# Hex_Motor_Module.net
KiCad netlist of a schematic drawn in EAGLE
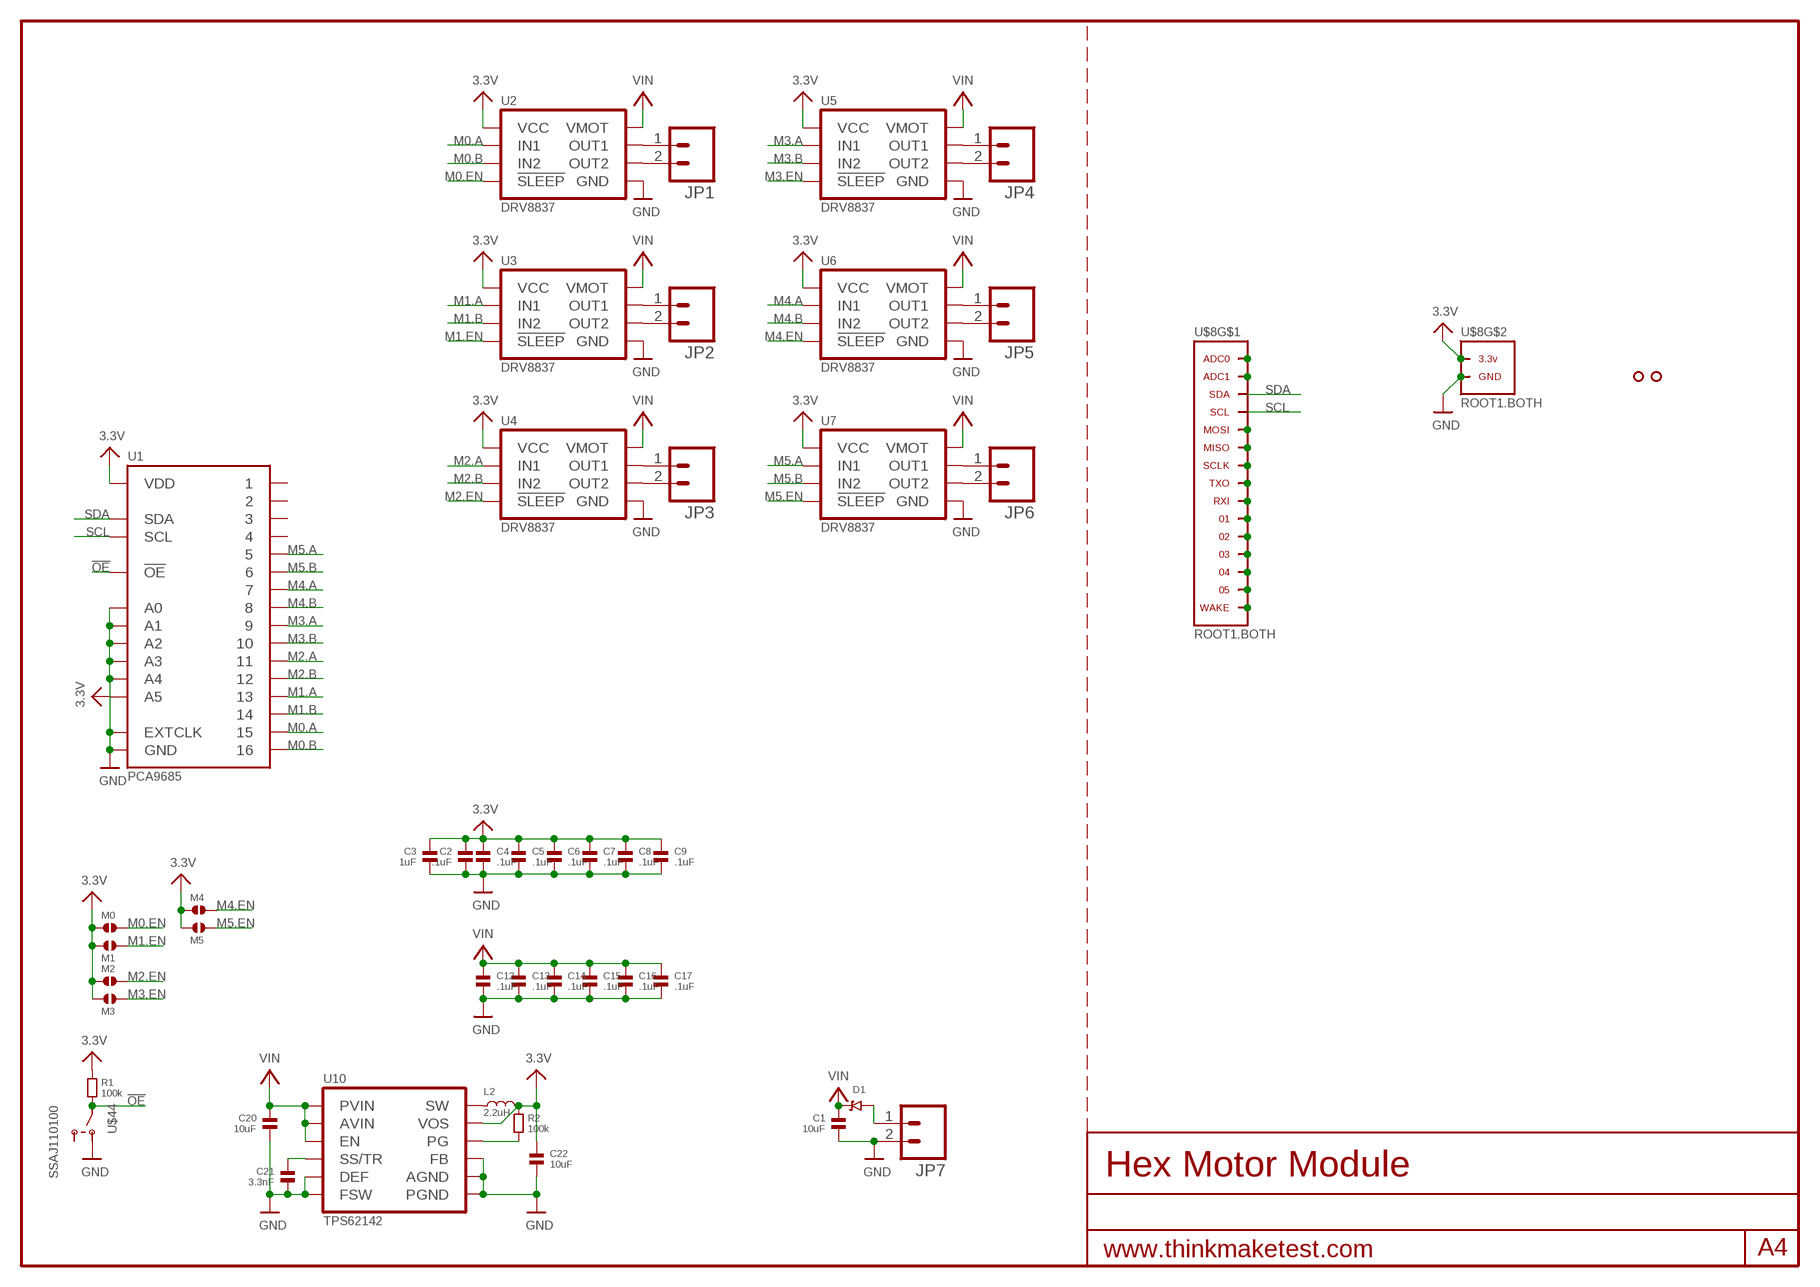
[diagram p0: schematic, sheet 1]

(export (version "E")
  (design (tool "Eeschema 10.0.6"))
  (components
    (comp (ref "C1")
      (value "10uF")
      (footprint "eagle-import:1206")
      (libsource (lib "eagle-import") (part "CAPACITOR.1206"))
    )
    (comp (ref "C2")
      (value ".1uF")
      (footprint "eagle-import:0603")
      (libsource (lib "eagle-import") (part "CAPACITOR.0603"))
    )
    (comp (ref "C3")
      (value "1uF")
      (footprint "eagle-import:0603")
      (libsource (lib "eagle-import") (part "CAPACITOR.0603"))
    )
    (comp (ref "C4")
      (value ".1uF")
      (footprint "eagle-import:0402")
      (libsource (lib "eagle-import") (part "CAPACITOR.0402"))
    )
    (comp (ref "C5")
      (value ".1uF")
      (footprint "eagle-import:0402")
      (libsource (lib "eagle-import") (part "CAPACITOR.0402"))
    )
    (comp (ref "C6")
      (value ".1uF")
      (footprint "eagle-import:0402")
      (libsource (lib "eagle-import") (part "CAPACITOR.0402"))
    )
    (comp (ref "C7")
      (value ".1uF")
      (footprint "eagle-import:0402")
      (libsource (lib "eagle-import") (part "CAPACITOR.0402"))
    )
    (comp (ref "C8")
      (value ".1uF")
      (footprint "eagle-import:0402")
      (libsource (lib "eagle-import") (part "CAPACITOR.0402"))
    )
    (comp (ref "C9")
      (value ".1uF")
      (footprint "eagle-import:0402")
      (libsource (lib "eagle-import") (part "CAPACITOR.0402"))
    )
    (comp (ref "C12")
      (value ".1uF")
      (footprint "eagle-import:0402")
      (libsource (lib "eagle-import") (part "CAPACITOR.0402"))
    )
    (comp (ref "C13")
      (value ".1uF")
      (footprint "eagle-import:0402")
      (libsource (lib "eagle-import") (part "CAPACITOR.0402"))
    )
    (comp (ref "C14")
      (value ".1uF")
      (footprint "eagle-import:0402")
      (libsource (lib "eagle-import") (part "CAPACITOR.0402"))
    )
    (comp (ref "C15")
      (value ".1uF")
      (footprint "eagle-import:0402")
      (libsource (lib "eagle-import") (part "CAPACITOR.0402"))
    )
    (comp (ref "C16")
      (value ".1uF")
      (footprint "eagle-import:0402")
      (libsource (lib "eagle-import") (part "CAPACITOR.0402"))
    )
    (comp (ref "C17")
      (value ".1uF")
      (footprint "eagle-import:0402")
      (libsource (lib "eagle-import") (part "CAPACITOR.0402"))
    )
    (comp (ref "C20")
      (value "10uF")
      (footprint "eagle-import:0805")
      (libsource (lib "eagle-import") (part "CAPACITOR.0805"))
    )
    (comp (ref "C21")
      (value "3.3nF")
      (footprint "eagle-import:0603")
      (libsource (lib "eagle-import") (part "CAPACITOR.0603"))
    )
    (comp (ref "C22")
      (value "10uF")
      (footprint "eagle-import:0805")
      (libsource (lib "eagle-import") (part "CAPACITOR.0805"))
    )
    (comp (ref "D1")
      (value "DIODE[SCHOTKY]-SOD123W")
      (footprint "eagle-import:SOD123W")
      (libsource (lib "eagle-import") (part "DIODE[SCHOTKY]-SOD123W"))
    )
    (comp (ref "JP1")
      (value "M023.5MM_LOCK")
      (footprint "eagle-import:SCREWTERMINAL-3.5MM-2_LOCK")
      (libsource (lib "eagle-import") (part "M023.5MM_LOCK"))
    )
    (comp (ref "JP2")
      (value "M023.5MM_LOCK")
      (footprint "eagle-import:SCREWTERMINAL-3.5MM-2_LOCK")
      (libsource (lib "eagle-import") (part "M023.5MM_LOCK"))
    )
    (comp (ref "JP3")
      (value "M023.5MM_LOCK")
      (footprint "eagle-import:SCREWTERMINAL-3.5MM-2_LOCK")
      (libsource (lib "eagle-import") (part "M023.5MM_LOCK"))
    )
    (comp (ref "JP4")
      (value "M023.5MM_LOCK")
      (footprint "eagle-import:SCREWTERMINAL-3.5MM-2_LOCK")
      (libsource (lib "eagle-import") (part "M023.5MM_LOCK"))
    )
    (comp (ref "JP5")
      (value "M023.5MM_LOCK")
      (footprint "eagle-import:SCREWTERMINAL-3.5MM-2_LOCK")
      (libsource (lib "eagle-import") (part "M023.5MM_LOCK"))
    )
    (comp (ref "JP6")
      (value "M023.5MM_LOCK")
      (footprint "eagle-import:SCREWTERMINAL-3.5MM-2_LOCK")
      (libsource (lib "eagle-import") (part "M023.5MM_LOCK"))
    )
    (comp (ref "JP7")
      (value "M023.5MM_LOCK")
      (footprint "eagle-import:SCREWTERMINAL-3.5MM-2_LOCK")
      (libsource (lib "eagle-import") (part "M023.5MM_LOCK"))
    )
    (comp (ref "L2")
      (value "2.2uH")
      (footprint "eagle-import:SRP4020")
      (libsource (lib "eagle-import") (part "INDUCTOR-SRP4020"))
    )
    (comp (ref "M0")
      (value "SOLDERJUMPER.2.LRG.PASTE")
      (footprint "eagle-import:2.LRG.PASTE")
      (libsource (lib "eagle-import") (part "SOLDERJUMPER.2.LRG.PASTE"))
    )
    (comp (ref "M1")
      (value "SOLDERJUMPER.2.LRG.PASTE")
      (footprint "eagle-import:2.LRG.PASTE")
      (libsource (lib "eagle-import") (part "SOLDERJUMPER.2.LRG.PASTE"))
    )
    (comp (ref "M2")
      (value "SOLDERJUMPER.2.LRG.PASTE")
      (footprint "eagle-import:2.LRG.PASTE")
      (libsource (lib "eagle-import") (part "SOLDERJUMPER.2.LRG.PASTE"))
    )
    (comp (ref "M3")
      (value "SOLDERJUMPER.2.LRG.PASTE")
      (footprint "eagle-import:2.LRG.PASTE")
      (libsource (lib "eagle-import") (part "SOLDERJUMPER.2.LRG.PASTE"))
    )
    (comp (ref "M4")
      (value "SOLDERJUMPER.2.LRG.PASTE")
      (footprint "eagle-import:2.LRG.PASTE")
      (libsource (lib "eagle-import") (part "SOLDERJUMPER.2.LRG.PASTE"))
    )
    (comp (ref "M5")
      (value "SOLDERJUMPER.2.LRG.PASTE")
      (footprint "eagle-import:2.LRG.PASTE")
      (libsource (lib "eagle-import") (part "SOLDERJUMPER.2.LRG.PASTE"))
    )
    (comp (ref "R1")
      (value "100k")
      (footprint "eagle-import:0603")
      (libsource (lib "eagle-import") (part "RESISTOR.0603"))
    )
    (comp (ref "R2")
      (value "100k")
      (footprint "eagle-import:0603")
      (libsource (lib "eagle-import") (part "RESISTOR.0603"))
    )
    (comp (ref "U$3")
      (value "HOLE.2MM")
      (footprint "eagle-import:2MM")
      (libsource (lib "eagle-import") (part "HOLE.2MM"))
    )
    (comp (ref "U$4")
      (value "HOLE.2MM")
      (footprint "eagle-import:2MM")
      (libsource (lib "eagle-import") (part "HOLE.2MM"))
    )
    (comp (ref "U$8")
      (value "ROOT1.BOTH")
      (footprint "eagle-import:ROOT1.BOTH")
      (libsource (lib "eagle-import") (part "ROOT1.BOTH"))
    )
    (comp (ref "U$44")
      (value "SSAJ110100")
      (footprint "eagle-import:SSAJ110100")
      (libsource (lib "eagle-import") (part "SSAJ110100"))
    )
    (comp (ref "U1")
      (value "PCA9685")
      (footprint "eagle-import:HVQFN28")
      (libsource (lib "eagle-import") (part "PCA9685"))
    )
    (comp (ref "U2")
      (value "DRV8837")
      (footprint "eagle-import:DSG")
      (libsource (lib "eagle-import") (part "DRV8837"))
    )
    (comp (ref "U3")
      (value "DRV8837")
      (footprint "eagle-import:DSG")
      (libsource (lib "eagle-import") (part "DRV8837"))
    )
    (comp (ref "U4")
      (value "DRV8837")
      (footprint "eagle-import:DSG")
      (libsource (lib "eagle-import") (part "DRV8837"))
    )
    (comp (ref "U5")
      (value "DRV8837")
      (footprint "eagle-import:DSG")
      (libsource (lib "eagle-import") (part "DRV8837"))
    )
    (comp (ref "U6")
      (value "DRV8837")
      (footprint "eagle-import:DSG")
      (libsource (lib "eagle-import") (part "DRV8837"))
    )
    (comp (ref "U7")
      (value "DRV8837")
      (footprint "eagle-import:DSG")
      (libsource (lib "eagle-import") (part "DRV8837"))
    )
    (comp (ref "U10")
      (value "TPS62142")
      (footprint "eagle-import:RGT")
      (libsource (lib "eagle-import") (part "TPS6214X"))
    )
  )
  (nets
    (net (code "1") (name "/M0.A") (class "Default")
      (node (ref "U1") (pin "21") (pinfunction "15_21") (pintype "bidirectional"))
      (node (ref "U2") (pin "6") (pinfunction "IN1_6") (pintype "bidirectional"))
    )
    (net (code "2") (name "/M0.B") (class "Default")
      (node (ref "U1") (pin "22") (pinfunction "16_22") (pintype "bidirectional"))
      (node (ref "U2") (pin "5") (pinfunction "IN2_5") (pintype "bidirectional"))
    )
    (net (code "3") (name "/M0.EN") (class "Default")
      (node (ref "M0") (pin "2") (pinfunction "2_2") (pintype "bidirectional"))
      (node (ref "U2") (pin "7") (pinfunction "~{SLEEP}_7") (pintype "bidirectional"))
    )
    (net (code "4") (name "/M1.A") (class "Default")
      (node (ref "U1") (pin "19") (pinfunction "13_19") (pintype "bidirectional"))
      (node (ref "U3") (pin "6") (pinfunction "IN1_6") (pintype "bidirectional"))
    )
    (net (code "5") (name "/M1.B") (class "Default")
      (node (ref "U1") (pin "20") (pinfunction "14_20") (pintype "bidirectional"))
      (node (ref "U3") (pin "5") (pinfunction "IN2_5") (pintype "bidirectional"))
    )
    (net (code "6") (name "/M1.EN") (class "Default")
      (node (ref "M1") (pin "2") (pinfunction "2_2") (pintype "bidirectional"))
      (node (ref "U3") (pin "7") (pinfunction "~{SLEEP}_7") (pintype "bidirectional"))
    )
    (net (code "7") (name "/M2.A") (class "Default")
      (node (ref "U1") (pin "17") (pinfunction "11_17") (pintype "bidirectional"))
      (node (ref "U4") (pin "6") (pinfunction "IN1_6") (pintype "bidirectional"))
    )
    (net (code "8") (name "/M2.B") (class "Default")
      (node (ref "U1") (pin "18") (pinfunction "12_18") (pintype "bidirectional"))
      (node (ref "U4") (pin "5") (pinfunction "IN2_5") (pintype "bidirectional"))
    )
    (net (code "9") (name "/M2.EN") (class "Default")
      (node (ref "M2") (pin "2") (pinfunction "2_2") (pintype "bidirectional"))
      (node (ref "U4") (pin "7") (pinfunction "~{SLEEP}_7") (pintype "bidirectional"))
    )
    (net (code "10") (name "/M3.A") (class "Default")
      (node (ref "U1") (pin "15") (pinfunction "9_15") (pintype "bidirectional"))
      (node (ref "U5") (pin "6") (pinfunction "IN1_6") (pintype "bidirectional"))
    )
    (net (code "11") (name "/M3.B") (class "Default")
      (node (ref "U1") (pin "16") (pinfunction "10_16") (pintype "bidirectional"))
      (node (ref "U5") (pin "5") (pinfunction "IN2_5") (pintype "bidirectional"))
    )
    (net (code "12") (name "/M3.EN") (class "Default")
      (node (ref "M3") (pin "2") (pinfunction "2_2") (pintype "bidirectional"))
      (node (ref "U5") (pin "7") (pinfunction "~{SLEEP}_7") (pintype "bidirectional"))
    )
    (net (code "13") (name "/M4.A") (class "Default")
      (node (ref "U1") (pin "12") (pinfunction "7_12") (pintype "bidirectional"))
      (node (ref "U6") (pin "6") (pinfunction "IN1_6") (pintype "bidirectional"))
    )
    (net (code "14") (name "/M4.B") (class "Default")
      (node (ref "U1") (pin "13") (pinfunction "8_13") (pintype "bidirectional"))
      (node (ref "U6") (pin "5") (pinfunction "IN2_5") (pintype "bidirectional"))
    )
    (net (code "15") (name "/M4.EN") (class "Default")
      (node (ref "M4") (pin "2") (pinfunction "2_2") (pintype "bidirectional"))
      (node (ref "U6") (pin "7") (pinfunction "~{SLEEP}_7") (pintype "bidirectional"))
    )
    (net (code "16") (name "/M5.A") (class "Default")
      (node (ref "U1") (pin "10") (pinfunction "5_10") (pintype "bidirectional"))
      (node (ref "U7") (pin "6") (pinfunction "IN1_6") (pintype "bidirectional"))
    )
    (net (code "17") (name "/M5.B") (class "Default")
      (node (ref "U1") (pin "11") (pinfunction "6_11") (pintype "bidirectional"))
      (node (ref "U7") (pin "5") (pinfunction "IN2_5") (pintype "bidirectional"))
    )
    (net (code "18") (name "/M5.EN") (class "Default")
      (node (ref "M5") (pin "2") (pinfunction "2_2") (pintype "bidirectional"))
      (node (ref "U7") (pin "7") (pinfunction "~{SLEEP}_7") (pintype "bidirectional"))
    )
    (net (code "19") (name "/SCL") (class "Default")
      (node (ref "U$8") (pin "SCL") (pinfunction "SCL_SCL") (pintype "bidirectional"))
      (node (ref "U$8") (pin "SCL@1") (pinfunction "SCL_SCL@1") (pintype "bidirectional"))
      (node (ref "U$8") (pin "SCL@VIA") (pinfunction "SCL_SCL@VIA") (pintype "bidirectional"))
      (node (ref "U1") (pin "26") (pinfunction "SCL_26") (pintype "bidirectional"))
    )
    (net (code "20") (name "/SDA") (class "Default")
      (node (ref "U$8") (pin "SDA") (pinfunction "SDA_SDA") (pintype "bidirectional"))
      (node (ref "U$8") (pin "SDA@1") (pinfunction "SDA_SDA@1") (pintype "bidirectional"))
      (node (ref "U$8") (pin "SDA@VIA") (pinfunction "SDA_SDA@VIA") (pintype "bidirectional"))
      (node (ref "U1") (pin "27") (pinfunction "SDA_27") (pintype "bidirectional"))
    )
    (net (code "21") (name "/~{OE}") (class "Default")
      (node (ref "R1") (pin "2") (pinfunction "2_2") (pintype "bidirectional"))
      (node (ref "U$44") (pin "C") (pinfunction "1_C") (pintype "bidirectional"))
      (node (ref "U1") (pin "23") (pinfunction "~{OE}_23") (pintype "bidirectional"))
    )
    (net (code "22") (name "3.3V") (class "Default")
      (node (ref "C2") (pin "1") (pinfunction "1_1") (pintype "bidirectional"))
      (node (ref "C22") (pin "1") (pinfunction "1_1") (pintype "bidirectional"))
      (node (ref "C3") (pin "1") (pinfunction "1_1") (pintype "bidirectional"))
      (node (ref "C4") (pin "1") (pinfunction "1_1") (pintype "bidirectional"))
      (node (ref "C5") (pin "1") (pinfunction "1_1") (pintype "bidirectional"))
      (node (ref "C6") (pin "1") (pinfunction "1_1") (pintype "bidirectional"))
      (node (ref "C7") (pin "1") (pinfunction "1_1") (pintype "bidirectional"))
      (node (ref "C8") (pin "1") (pinfunction "1_1") (pintype "bidirectional"))
      (node (ref "C9") (pin "1") (pinfunction "1_1") (pintype "bidirectional"))
      (node (ref "L2") (pin "2") (pinfunction "2_2") (pintype "passive"))
      (node (ref "M0") (pin "1") (pinfunction "1_1") (pintype "bidirectional"))
      (node (ref "M1") (pin "1") (pinfunction "1_1") (pintype "bidirectional"))
      (node (ref "M2") (pin "1") (pinfunction "1_1") (pintype "bidirectional"))
      (node (ref "M3") (pin "1") (pinfunction "1_1") (pintype "bidirectional"))
      (node (ref "M4") (pin "1") (pinfunction "1_1") (pintype "bidirectional"))
      (node (ref "M5") (pin "1") (pinfunction "1_1") (pintype "bidirectional"))
      (node (ref "R1") (pin "1") (pinfunction "1_1") (pintype "bidirectional"))
      (node (ref "R2") (pin "1") (pinfunction "1_1") (pintype "bidirectional"))
      (node (ref "U$8") (pin "3.3V@1") (pinfunction "3.3V_3.3V@1") (pintype "bidirectional"))
      (node (ref "U$8") (pin "3.3V@10") (pinfunction "3.3V_3.3V@10") (pintype "bidirectional"))
      (node (ref "U$8") (pin "3.3V@2") (pinfunction "3.3V_3.3V@2") (pintype "bidirectional"))
      (node (ref "U$8") (pin "3.3V@3") (pinfunction "3.3V_3.3V@3") (pintype "bidirectional"))
      (node (ref "U$8") (pin "3.3V@4") (pinfunction "3.3V_3.3V@4") (pintype "bidirectional"))
      (node (ref "U$8") (pin "3.3V@5") (pinfunction "3.3V_3.3V@5") (pintype "bidirectional"))
      (node (ref "U$8") (pin "3.3V@6") (pinfunction "3.3V_3.3V@6") (pintype "bidirectional"))
      (node (ref "U$8") (pin "3.3V@7") (pinfunction "3.3V_3.3V@7") (pintype "bidirectional"))
      (node (ref "U$8") (pin "3.3V@8") (pinfunction "3.3V_3.3V@8") (pintype "bidirectional"))
      (node (ref "U$8") (pin "3.3V@9") (pinfunction "3.3V_3.3V@9") (pintype "bidirectional"))
      (node (ref "U$8") (pin "3.3V@VIA") (pinfunction "3.3V_3.3V@VIA") (pintype "bidirectional"))
      (node (ref "U1") (pin "24") (pinfunction "A5_24") (pintype "bidirectional"))
      (node (ref "U1") (pin "28") (pinfunction "VDD_28") (pintype "bidirectional"))
      (node (ref "U10") (pin "14") (pinfunction "VOS_14") (pintype "bidirectional"))
      (node (ref "U2") (pin "8") (pinfunction "VCC_8") (pintype "bidirectional"))
      (node (ref "U3") (pin "8") (pinfunction "VCC_8") (pintype "bidirectional"))
      (node (ref "U4") (pin "8") (pinfunction "VCC_8") (pintype "bidirectional"))
      (node (ref "U5") (pin "8") (pinfunction "VCC_8") (pintype "bidirectional"))
      (node (ref "U6") (pin "8") (pinfunction "VCC_8") (pintype "bidirectional"))
      (node (ref "U7") (pin "8") (pinfunction "VCC_8") (pintype "bidirectional"))
    )
    (net (code "23") (name "GND") (class "Default")
      (node (ref "C1") (pin "2") (pinfunction "2_2") (pintype "bidirectional"))
      (node (ref "C12") (pin "2") (pinfunction "2_2") (pintype "bidirectional"))
      (node (ref "C13") (pin "2") (pinfunction "2_2") (pintype "bidirectional"))
      (node (ref "C14") (pin "2") (pinfunction "2_2") (pintype "bidirectional"))
      (node (ref "C15") (pin "2") (pinfunction "2_2") (pintype "bidirectional"))
      (node (ref "C16") (pin "2") (pinfunction "2_2") (pintype "bidirectional"))
      (node (ref "C17") (pin "2") (pinfunction "2_2") (pintype "bidirectional"))
      (node (ref "C2") (pin "2") (pinfunction "2_2") (pintype "bidirectional"))
      (node (ref "C20") (pin "2") (pinfunction "2_2") (pintype "bidirectional"))
      (node (ref "C21") (pin "2") (pinfunction "2_2") (pintype "bidirectional"))
      (node (ref "C22") (pin "2") (pinfunction "2_2") (pintype "bidirectional"))
      (node (ref "C3") (pin "2") (pinfunction "2_2") (pintype "bidirectional"))
      (node (ref "C4") (pin "2") (pinfunction "2_2") (pintype "bidirectional"))
      (node (ref "C5") (pin "2") (pinfunction "2_2") (pintype "bidirectional"))
      (node (ref "C6") (pin "2") (pinfunction "2_2") (pintype "bidirectional"))
      (node (ref "C7") (pin "2") (pinfunction "2_2") (pintype "bidirectional"))
      (node (ref "C8") (pin "2") (pinfunction "2_2") (pintype "bidirectional"))
      (node (ref "C9") (pin "2") (pinfunction "2_2") (pintype "bidirectional"))
      (node (ref "JP7") (pin "2") (pinfunction "2_2") (pintype "passive"))
      (node (ref "U$44") (pin "1") (pinfunction "2_1") (pintype "bidirectional"))
      (node (ref "U$8") (pin "GND@1") (pinfunction "GND_GND@1") (pintype "bidirectional"))
      (node (ref "U$8") (pin "GND@10") (pinfunction "GND_GND@10") (pintype "bidirectional"))
      (node (ref "U$8") (pin "GND@11") (pinfunction "GND_GND@11") (pintype "bidirectional"))
      (node (ref "U$8") (pin "GND@12") (pinfunction "GND_GND@12") (pintype "bidirectional"))
      (node (ref "U$8") (pin "GND@13") (pinfunction "GND_GND@13") (pintype "bidirectional"))
      (node (ref "U$8") (pin "GND@14") (pinfunction "GND_GND@14") (pintype "bidirectional"))
      (node (ref "U$8") (pin "GND@15") (pinfunction "GND_GND@15") (pintype "bidirectional"))
      (node (ref "U$8") (pin "GND@16") (pinfunction "GND_GND@16") (pintype "bidirectional"))
      (node (ref "U$8") (pin "GND@17") (pinfunction "GND_GND@17") (pintype "bidirectional"))
      (node (ref "U$8") (pin "GND@18") (pinfunction "GND_GND@18") (pintype "bidirectional"))
      (node (ref "U$8") (pin "GND@19") (pinfunction "GND_GND@19") (pintype "bidirectional"))
      (node (ref "U$8") (pin "GND@2") (pinfunction "GND_GND@2") (pintype "bidirectional"))
      (node (ref "U$8") (pin "GND@20") (pinfunction "GND_GND@20") (pintype "bidirectional"))
      (node (ref "U$8") (pin "GND@3") (pinfunction "GND_GND@3") (pintype "bidirectional"))
      (node (ref "U$8") (pin "GND@4") (pinfunction "GND_GND@4") (pintype "bidirectional"))
      (node (ref "U$8") (pin "GND@5") (pinfunction "GND_GND@5") (pintype "bidirectional"))
      (node (ref "U$8") (pin "GND@6") (pinfunction "GND_GND@6") (pintype "bidirectional"))
      (node (ref "U$8") (pin "GND@7") (pinfunction "GND_GND@7") (pintype "bidirectional"))
      (node (ref "U$8") (pin "GND@8") (pinfunction "GND_GND@8") (pintype "bidirectional"))
      (node (ref "U$8") (pin "GND@9") (pinfunction "GND_GND@9") (pintype "bidirectional"))
      (node (ref "U$8") (pin "GND@VIA") (pinfunction "GND_GND@VIA") (pintype "bidirectional"))
      (node (ref "U1") (pin "1") (pinfunction "A0_1") (pintype "bidirectional"))
      (node (ref "U1") (pin "14") (pinfunction "GND_14") (pintype "bidirectional"))
      (node (ref "U1") (pin "2") (pinfunction "A1_2") (pintype "bidirectional"))
      (node (ref "U1") (pin "25") (pinfunction "EXTCLK_25") (pintype "bidirectional"))
      (node (ref "U1") (pin "3") (pinfunction "A2_3") (pintype "bidirectional"))
      (node (ref "U1") (pin "4") (pinfunction "A3_4") (pintype "bidirectional"))
      (node (ref "U1") (pin "5") (pinfunction "A4_5") (pintype "bidirectional"))
      (node (ref "U1") (pin "PAD") (pinfunction "GND_PAD") (pintype "bidirectional"))
      (node (ref "U10") (pin "15") (pinfunction "PGND_15") (pintype "bidirectional"))
      (node (ref "U10") (pin "16") (pinfunction "PGND_16") (pintype "bidirectional"))
      (node (ref "U10") (pin "5") (pinfunction "FB_5") (pintype "bidirectional"))
      (node (ref "U10") (pin "6") (pinfunction "AGND_6") (pintype "bidirectional"))
      (node (ref "U10") (pin "7") (pinfunction "FSW_7") (pintype "bidirectional"))
      (node (ref "U10") (pin "8") (pinfunction "DEF_8") (pintype "bidirectional"))
      (node (ref "U10") (pin "PAD") (pinfunction "AGND_PAD") (pintype "bidirectional"))
      (node (ref "U2") (pin "4") (pinfunction "GND_4") (pintype "bidirectional"))
      (node (ref "U2") (pin "PAD") (pinfunction "GND_PAD") (pintype "bidirectional"))
      (node (ref "U3") (pin "4") (pinfunction "GND_4") (pintype "bidirectional"))
      (node (ref "U3") (pin "PAD") (pinfunction "GND_PAD") (pintype "bidirectional"))
      (node (ref "U4") (pin "4") (pinfunction "GND_4") (pintype "bidirectional"))
      (node (ref "U4") (pin "PAD") (pinfunction "GND_PAD") (pintype "bidirectional"))
      (node (ref "U5") (pin "4") (pinfunction "GND_4") (pintype "bidirectional"))
      (node (ref "U5") (pin "PAD") (pinfunction "GND_PAD") (pintype "bidirectional"))
      (node (ref "U6") (pin "4") (pinfunction "GND_4") (pintype "bidirectional"))
      (node (ref "U6") (pin "PAD") (pinfunction "GND_PAD") (pintype "bidirectional"))
      (node (ref "U7") (pin "4") (pinfunction "GND_4") (pintype "bidirectional"))
      (node (ref "U7") (pin "PAD") (pinfunction "GND_PAD") (pintype "bidirectional"))
    )
    (net (code "24") (name "Net-(D1-1)") (class "Default")
      (node (ref "D1") (pin "P$1") (pinfunction "1_P$1") (pintype "bidirectional"))
      (node (ref "JP7") (pin "1") (pinfunction "1_1") (pintype "passive"))
    )
    (net (code "25") (name "Net-(L2-Pad1)") (class "Default")
      (node (ref "L2") (pin "1") (pinfunction "1_1") (pintype "passive"))
      (node (ref "U10") (pin "1") (pinfunction "SW_1") (pintype "bidirectional"))
      (node (ref "U10") (pin "2") (pinfunction "SW_2") (pintype "bidirectional"))
      (node (ref "U10") (pin "3") (pinfunction "SW_3") (pintype "bidirectional"))
    )
    (net (code "26") (name "Net-(U$8-PadADC0)") (class "Default")
      (node (ref "U$8") (pin "ADC0") (pinfunction "ADC0_ADC0") (pintype "bidirectional"))
      (node (ref "U$8") (pin "ADC0@1") (pinfunction "ADC0_ADC0@1") (pintype "bidirectional"))
      (node (ref "U$8") (pin "ADC0@VIA") (pinfunction "ADC0_ADC0@VIA") (pintype "bidirectional"))
    )
    (net (code "27") (name "Net-(U$8-PadADC1)") (class "Default")
      (node (ref "U$8") (pin "ADC1") (pinfunction "ADC1_ADC1") (pintype "bidirectional"))
      (node (ref "U$8") (pin "ADC1@1") (pinfunction "ADC1_ADC1@1") (pintype "bidirectional"))
      (node (ref "U$8") (pin "ADC1@VIA") (pinfunction "ADC1_ADC1@VIA") (pintype "bidirectional"))
    )
    (net (code "28") (name "Net-(U$8-PadMISO)") (class "Default")
      (node (ref "U$8") (pin "MISO") (pinfunction "MISO_MISO") (pintype "bidirectional"))
      (node (ref "U$8") (pin "MISO@1") (pinfunction "MISO_MISO@1") (pintype "bidirectional"))
      (node (ref "U$8") (pin "MISO@VIA") (pinfunction "MISO_MISO@VIA") (pintype "bidirectional"))
    )
    (net (code "29") (name "Net-(U$8-PadMOSI)") (class "Default")
      (node (ref "U$8") (pin "MOSI") (pinfunction "MOSI_MOSI") (pintype "bidirectional"))
      (node (ref "U$8") (pin "MOSI@1") (pinfunction "MOSI_MOSI@1") (pintype "bidirectional"))
      (node (ref "U$8") (pin "MOSI@VIA") (pinfunction "MOSI_MOSI@VIA") (pintype "bidirectional"))
    )
    (net (code "30") (name "Net-(U$8-PadSCLK)") (class "Default")
      (node (ref "U$8") (pin "SCLK") (pinfunction "SCLK_SCLK") (pintype "bidirectional"))
      (node (ref "U$8") (pin "SCLK@1") (pinfunction "SCLK_SCLK@1") (pintype "bidirectional"))
      (node (ref "U$8") (pin "SCLK@VIA") (pinfunction "SCLK_SCLK@VIA") (pintype "bidirectional"))
    )
    (net (code "31") (name "Net-(U$8-PadWAKE)") (class "Default")
      (node (ref "U$8") (pin "WAKE") (pinfunction "WAKE_WAKE") (pintype "bidirectional"))
      (node (ref "U$8") (pin "WAKE@1") (pinfunction "WAKE_WAKE@1") (pintype "bidirectional"))
      (node (ref "U$8") (pin "WAKE@VIA") (pinfunction "WAKE_WAKE@VIA") (pintype "bidirectional"))
    )
    (net (code "32") (name "Net-(U$8A-01-Pad03)") (class "Default")
      (node (ref "U$8") (pin "03") (pinfunction "01_03") (pintype "bidirectional"))
      (node (ref "U$8") (pin "03@1") (pinfunction "01_03@1") (pintype "bidirectional"))
      (node (ref "U$8") (pin "03@VIA") (pinfunction "01_03@VIA") (pintype "bidirectional"))
    )
    (net (code "33") (name "Net-(U$8A-02-Pad04)") (class "Default")
      (node (ref "U$8") (pin "04") (pinfunction "02_04") (pintype "bidirectional"))
      (node (ref "U$8") (pin "04@1") (pinfunction "02_04@1") (pintype "bidirectional"))
      (node (ref "U$8") (pin "04@VIA") (pinfunction "02_04@VIA") (pintype "bidirectional"))
    )
    (net (code "34") (name "Net-(U$8A-03-Pad05)") (class "Default")
      (node (ref "U$8") (pin "05") (pinfunction "03_05") (pintype "bidirectional"))
      (node (ref "U$8") (pin "05@1") (pinfunction "03_05@1") (pintype "bidirectional"))
      (node (ref "U$8") (pin "05@VIA") (pinfunction "03_05@VIA") (pintype "bidirectional"))
    )
    (net (code "35") (name "Net-(U$8A-04-Pad06)") (class "Default")
      (node (ref "U$8") (pin "06") (pinfunction "04_06") (pintype "bidirectional"))
      (node (ref "U$8") (pin "06@1") (pinfunction "04_06@1") (pintype "bidirectional"))
      (node (ref "U$8") (pin "06@VIA") (pinfunction "04_06@VIA") (pintype "bidirectional"))
    )
    (net (code "36") (name "Net-(U$8A-05-Pad07)") (class "Default")
      (node (ref "U$8") (pin "07") (pinfunction "05_07") (pintype "bidirectional"))
      (node (ref "U$8") (pin "07@1") (pinfunction "05_07@1") (pintype "bidirectional"))
      (node (ref "U$8") (pin "07@VIA") (pinfunction "05_07@VIA") (pintype "bidirectional"))
    )
    (net (code "37") (name "Net-(U$8A-RXI-Pad02)") (class "Default")
      (node (ref "U$8") (pin "02") (pinfunction "RXI_02") (pintype "bidirectional"))
      (node (ref "U$8") (pin "02@1") (pinfunction "RXI_02@1") (pintype "bidirectional"))
      (node (ref "U$8") (pin "02@VIA") (pinfunction "RXI_02@VIA") (pintype "bidirectional"))
    )
    (net (code "38") (name "Net-(U$8A-TXO-Pad01)") (class "Default")
      (node (ref "U$8") (pin "01") (pinfunction "TXO_01") (pintype "bidirectional"))
      (node (ref "U$8") (pin "01@1") (pinfunction "TXO_01@1") (pintype "bidirectional"))
      (node (ref "U$8") (pin "01@VIA") (pinfunction "TXO_01@VIA") (pintype "bidirectional"))
    )
    (net (code "39") (name "Net-(U2-OUT1)") (class "Default")
      (node (ref "JP1") (pin "1") (pinfunction "1_1") (pintype "passive"))
      (node (ref "U2") (pin "2") (pinfunction "OUT1_2") (pintype "bidirectional"))
    )
    (net (code "40") (name "Net-(U2-OUT2)") (class "Default")
      (node (ref "JP1") (pin "2") (pinfunction "2_2") (pintype "passive"))
      (node (ref "U2") (pin "3") (pinfunction "OUT2_3") (pintype "bidirectional"))
    )
    (net (code "41") (name "Net-(U3-OUT1)") (class "Default")
      (node (ref "JP2") (pin "1") (pinfunction "1_1") (pintype "passive"))
      (node (ref "U3") (pin "2") (pinfunction "OUT1_2") (pintype "bidirectional"))
    )
    (net (code "42") (name "Net-(U3-OUT2)") (class "Default")
      (node (ref "JP2") (pin "2") (pinfunction "2_2") (pintype "passive"))
      (node (ref "U3") (pin "3") (pinfunction "OUT2_3") (pintype "bidirectional"))
    )
    (net (code "43") (name "Net-(U4-OUT1)") (class "Default")
      (node (ref "JP3") (pin "1") (pinfunction "1_1") (pintype "passive"))
      (node (ref "U4") (pin "2") (pinfunction "OUT1_2") (pintype "bidirectional"))
    )
    (net (code "44") (name "Net-(U4-OUT2)") (class "Default")
      (node (ref "JP3") (pin "2") (pinfunction "2_2") (pintype "passive"))
      (node (ref "U4") (pin "3") (pinfunction "OUT2_3") (pintype "bidirectional"))
    )
    (net (code "45") (name "Net-(U5-OUT1)") (class "Default")
      (node (ref "JP4") (pin "1") (pinfunction "1_1") (pintype "passive"))
      (node (ref "U5") (pin "2") (pinfunction "OUT1_2") (pintype "bidirectional"))
    )
    (net (code "46") (name "Net-(U5-OUT2)") (class "Default")
      (node (ref "JP4") (pin "2") (pinfunction "2_2") (pintype "passive"))
      (node (ref "U5") (pin "3") (pinfunction "OUT2_3") (pintype "bidirectional"))
    )
    (net (code "47") (name "Net-(U6-OUT1)") (class "Default")
      (node (ref "JP5") (pin "1") (pinfunction "1_1") (pintype "passive"))
      (node (ref "U6") (pin "2") (pinfunction "OUT1_2") (pintype "bidirectional"))
    )
    (net (code "48") (name "Net-(U6-OUT2)") (class "Default")
      (node (ref "JP5") (pin "2") (pinfunction "2_2") (pintype "passive"))
      (node (ref "U6") (pin "3") (pinfunction "OUT2_3") (pintype "bidirectional"))
    )
    (net (code "49") (name "Net-(U7-OUT1)") (class "Default")
      (node (ref "JP6") (pin "1") (pinfunction "1_1") (pintype "passive"))
      (node (ref "U7") (pin "2") (pinfunction "OUT1_2") (pintype "bidirectional"))
    )
    (net (code "50") (name "Net-(U7-OUT2)") (class "Default")
      (node (ref "JP6") (pin "2") (pinfunction "2_2") (pintype "passive"))
      (node (ref "U7") (pin "3") (pinfunction "OUT2_3") (pintype "bidirectional"))
    )
    (net (code "51") (name "Net-(U10-PG)") (class "Default")
      (node (ref "R2") (pin "2") (pinfunction "2_2") (pintype "bidirectional"))
      (node (ref "U10") (pin "4") (pinfunction "PG_4") (pintype "bidirectional"))
    )
    (net (code "52") (name "Net-(U10-SS{slash}TR)") (class "Default")
      (node (ref "C21") (pin "1") (pinfunction "1_1") (pintype "bidirectional"))
      (node (ref "U10") (pin "9") (pinfunction "SS/TR_9") (pintype "bidirectional"))
    )
    (net (code "53") (name "VIN") (class "Default")
      (node (ref "C1") (pin "1") (pinfunction "1_1") (pintype "bidirectional"))
      (node (ref "C12") (pin "1") (pinfunction "1_1") (pintype "bidirectional"))
      (node (ref "C13") (pin "1") (pinfunction "1_1") (pintype "bidirectional"))
      (node (ref "C14") (pin "1") (pinfunction "1_1") (pintype "bidirectional"))
      (node (ref "C15") (pin "1") (pinfunction "1_1") (pintype "bidirectional"))
      (node (ref "C16") (pin "1") (pinfunction "1_1") (pintype "bidirectional"))
      (node (ref "C17") (pin "1") (pinfunction "1_1") (pintype "bidirectional"))
      (node (ref "C20") (pin "1") (pinfunction "1_1") (pintype "bidirectional"))
      (node (ref "D1") (pin "P$2") (pinfunction "2_P$2") (pintype "bidirectional"))
      (node (ref "U10") (pin "10") (pinfunction "AVIN_10") (pintype "bidirectional"))
      (node (ref "U10") (pin "11") (pinfunction "PVIN_11") (pintype "bidirectional"))
      (node (ref "U10") (pin "12") (pinfunction "PVIN_12") (pintype "bidirectional"))
      (node (ref "U10") (pin "13") (pinfunction "EN_13") (pintype "bidirectional"))
      (node (ref "U2") (pin "1") (pinfunction "VMOT_1") (pintype "bidirectional"))
      (node (ref "U3") (pin "1") (pinfunction "VMOT_1") (pintype "bidirectional"))
      (node (ref "U4") (pin "1") (pinfunction "VMOT_1") (pintype "bidirectional"))
      (node (ref "U5") (pin "1") (pinfunction "VMOT_1") (pintype "bidirectional"))
      (node (ref "U6") (pin "1") (pinfunction "VMOT_1") (pintype "bidirectional"))
      (node (ref "U7") (pin "1") (pinfunction "VMOT_1") (pintype "bidirectional"))
    )
    (net (code "54") (name "unconnected-(U$44-3-Pad2)") (class "Default")
      (node (ref "U$44") (pin "2") (pinfunction "3_2") (pintype "bidirectional"))
    )
    (net (code "55") (name "unconnected-(U1-1-Pad6)") (class "Default")
      (node (ref "U1") (pin "6") (pinfunction "1_6") (pintype "bidirectional"))
    )
    (net (code "56") (name "unconnected-(U1-2-Pad7)") (class "Default")
      (node (ref "U1") (pin "7") (pinfunction "2_7") (pintype "bidirectional"))
    )
    (net (code "57") (name "unconnected-(U1-3-Pad8)") (class "Default")
      (node (ref "U1") (pin "8") (pinfunction "3_8") (pintype "bidirectional"))
    )
    (net (code "58") (name "unconnected-(U1-4-Pad9)") (class "Default")
      (node (ref "U1") (pin "9") (pinfunction "4_9") (pintype "bidirectional"))
    )
  )
)
